# Smarttree_BMS_3_1.net
KiCad netlist of a schematic drawn in EAGLE
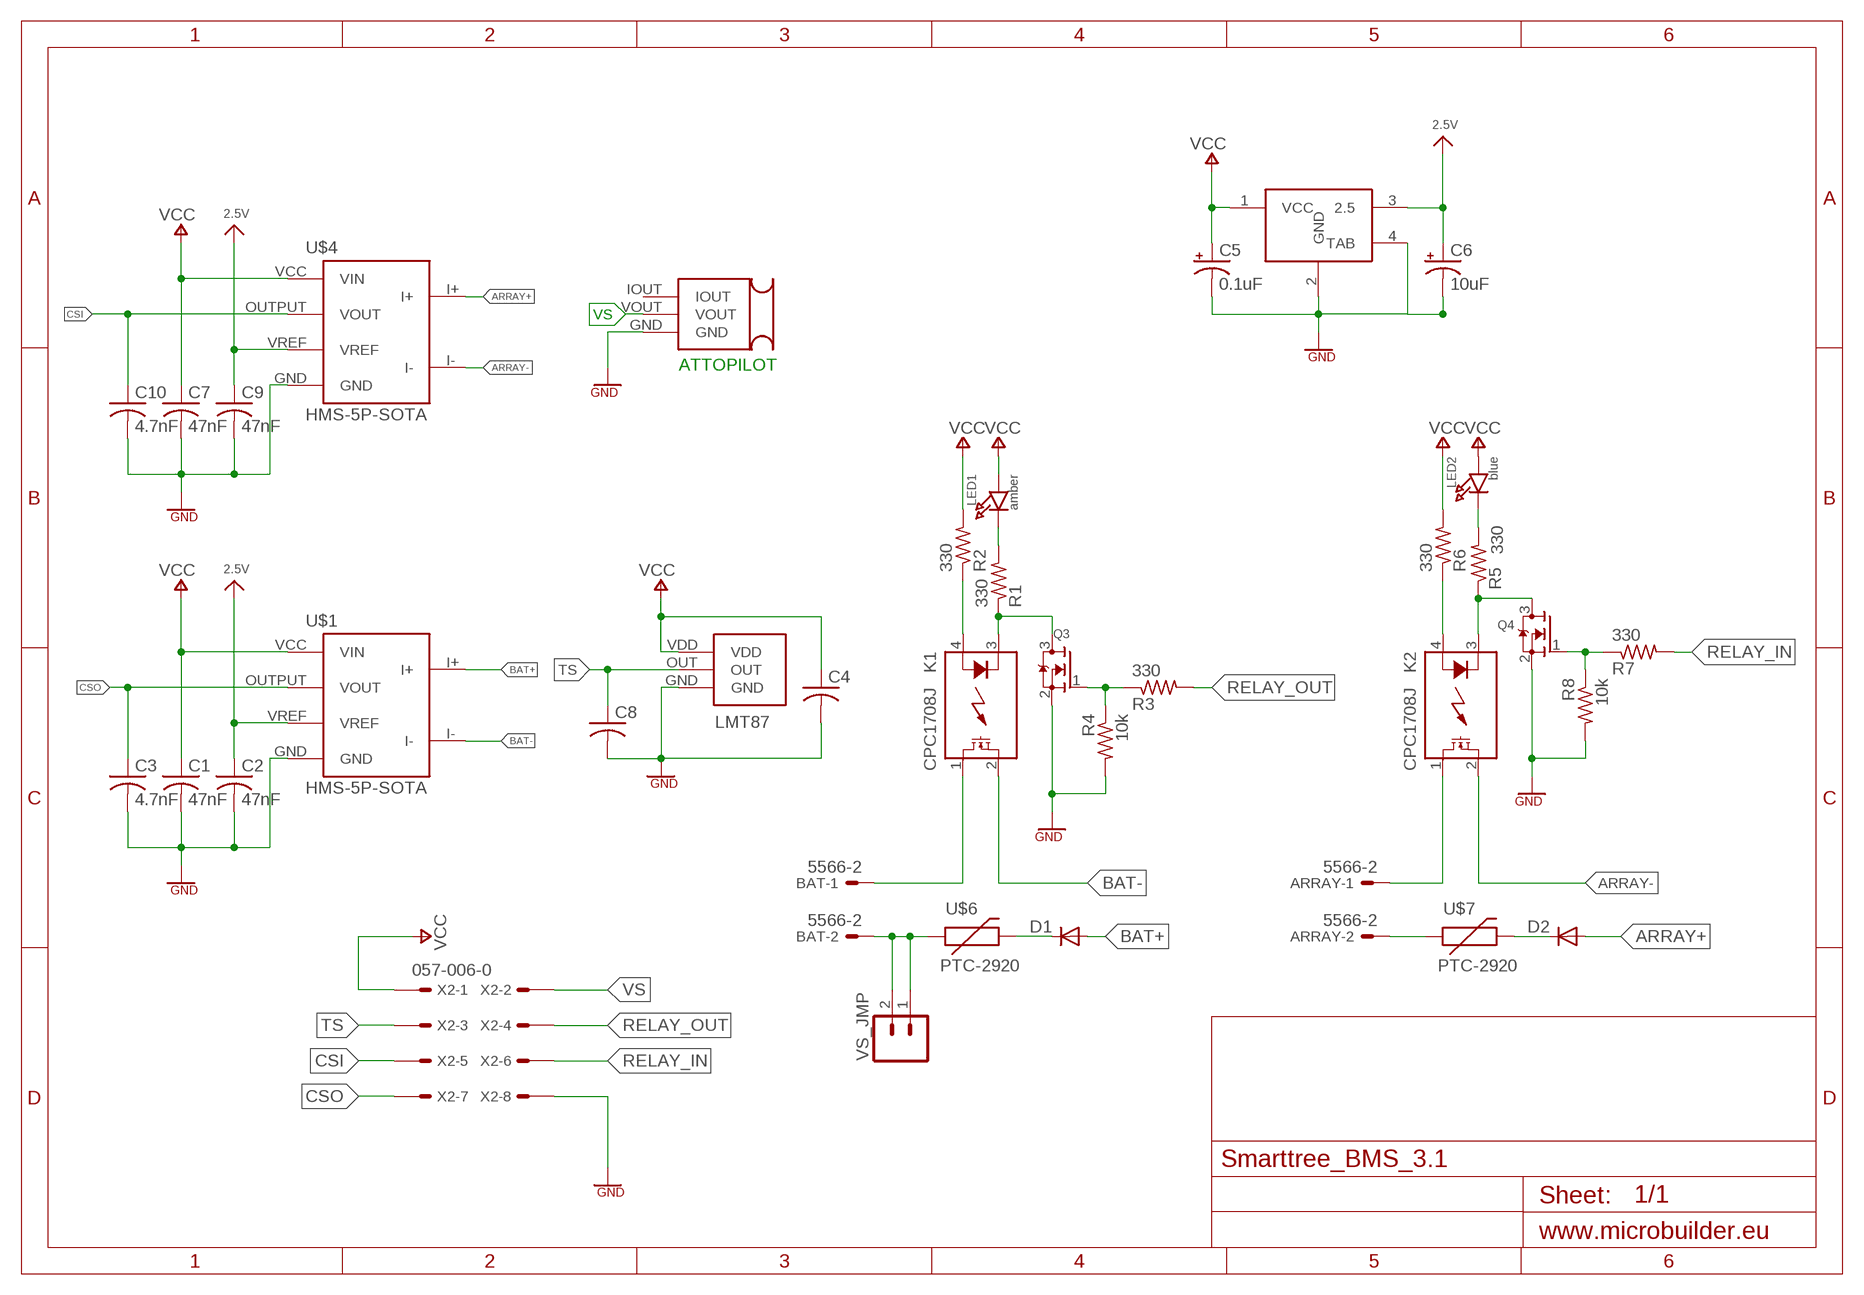
[diagram p0: schematic, sheet 1]

(export (version "E")
  (design (tool "Eeschema 10.0.6"))
  (components
    (comp (ref "ARRAY")
      (value "5566-2")
      (footprint "eagle-import:5566-2")
      (libsource (lib "eagle-import") (part "5566-2"))
    )
    (comp (ref "ATTOPILOT")
      (value "ATTOPILOT_VOLT")
      (footprint "eagle-import:TH_BKOT")
      (libsource (lib "eagle-import") (part "ATTOPILOT_VOLT"))
    )
    (comp (ref "BAT")
      (value "5566-2")
      (footprint "eagle-import:5566-2")
      (libsource (lib "eagle-import") (part "5566-2"))
    )
    (comp (ref "C1")
      (value "47nF")
      (footprint "eagle-import:C0805")
      (libsource (lib "eagle-import") (part "C-USC0805"))
    )
    (comp (ref "C2")
      (value "47nF")
      (footprint "eagle-import:C0805")
      (libsource (lib "eagle-import") (part "C-USC0805"))
    )
    (comp (ref "C3")
      (value "4.7nF")
      (footprint "eagle-import:C0805")
      (libsource (lib "eagle-import") (part "C-USC0805"))
    )
    (comp (ref "C4")
      (value "C-USC0805")
      (footprint "eagle-import:C0805")
      (libsource (lib "eagle-import") (part "C-USC0805"))
    )
    (comp (ref "C5")
      (value "0.1uF")
      (footprint "eagle-import:EIA3216")
      (libsource (lib "eagle-import") (part "10UF-TANT"))
    )
    (comp (ref "C6")
      (value "10uF")
      (footprint "eagle-import:EIA3216")
      (libsource (lib "eagle-import") (part "10UF-TANT"))
    )
    (comp (ref "C7")
      (value "47nF")
      (footprint "eagle-import:C0805")
      (libsource (lib "eagle-import") (part "C-USC0805"))
    )
    (comp (ref "C8")
      (value "C-USC0805")
      (footprint "eagle-import:C0805")
      (libsource (lib "eagle-import") (part "C-USC0805"))
    )
    (comp (ref "C9")
      (value "47nF")
      (footprint "eagle-import:C0805")
      (libsource (lib "eagle-import") (part "C-USC0805"))
    )
    (comp (ref "C10")
      (value "4.7nF")
      (footprint "eagle-import:C0805")
      (libsource (lib "eagle-import") (part "C-USC0805"))
    )
    (comp (ref "D1")
      (value "DIODE-SOD106-R")
      (footprint "eagle-import:SOD106-R")
      (libsource (lib "eagle-import") (part "DIODE-SOD106-R"))
    )
    (comp (ref "D2")
      (value "DIODE-SOD106-R")
      (footprint "eagle-import:SOD106-R")
      (libsource (lib "eagle-import") (part "DIODE-SOD106-R"))
    )
    (comp (ref "K1")
      (value "CPC1708J")
      (footprint "eagle-import:I4-PAC")
      (libsource (lib "eagle-import") (part "CPC1708J"))
    )
    (comp (ref "K2")
      (value "CPC1708J")
      (footprint "eagle-import:I4-PAC")
      (libsource (lib "eagle-import") (part "CPC1708J"))
    )
    (comp (ref "LED1")
      (value "amber")
      (footprint "eagle-import:CHIPLED_0805")
      (libsource (lib "eagle-import") (part "LED0805"))
    )
    (comp (ref "LED2")
      (value "blue")
      (footprint "eagle-import:CHIPLED_0805")
      (libsource (lib "eagle-import") (part "LED0805"))
    )
    (comp (ref "LM1117")
      (value "LM2937_SOT223")
      (footprint "eagle-import:SOT223")
      (libsource (lib "eagle-import") (part "LM2937_SOT223"))
    )
    (comp (ref "LMT87")
      (value "LMT87_PAC")
      (footprint "eagle-import:LMT87_TO")
      (libsource (lib "eagle-import") (part "LMT87_PAC"))
    )
    (comp (ref "Q3")
      (value "MOSFET-NREFLOW")
      (footprint "eagle-import:SOT23")
      (libsource (lib "eagle-import") (part "MOSFET-NREFLOW"))
    )
    (comp (ref "Q4")
      (value "MOSFET-NREFLOW")
      (footprint "eagle-import:SOT23")
      (libsource (lib "eagle-import") (part "MOSFET-NREFLOW"))
    )
    (comp (ref "R1")
      (value "330")
      (footprint "eagle-import:R0805")
      (libsource (lib "eagle-import") (part "R-US_R0805"))
    )
    (comp (ref "R2")
      (value "330")
      (footprint "eagle-import:R0805")
      (libsource (lib "eagle-import") (part "R-US_R0805"))
    )
    (comp (ref "R3")
      (value "330")
      (footprint "eagle-import:R0805")
      (libsource (lib "eagle-import") (part "R-US_R0805"))
    )
    (comp (ref "R4")
      (value "10k")
      (footprint "eagle-import:R0805")
      (libsource (lib "eagle-import") (part "R-US_R0805"))
    )
    (comp (ref "R5")
      (value "330")
      (footprint "eagle-import:R0805")
      (libsource (lib "eagle-import") (part "R-US_R0805"))
    )
    (comp (ref "R6")
      (value "330")
      (footprint "eagle-import:R0805")
      (libsource (lib "eagle-import") (part "R-US_R0805"))
    )
    (comp (ref "R7")
      (value "330")
      (footprint "eagle-import:R0805")
      (libsource (lib "eagle-import") (part "R-US_R0805"))
    )
    (comp (ref "R8")
      (value "10k")
      (footprint "eagle-import:R0805")
      (libsource (lib "eagle-import") (part "R-US_R0805"))
    )
    (comp (ref "U$1")
      (value "HMS-5P-SOTA")
      (footprint "eagle-import:SMD_CURR_SENSE")
      (libsource (lib "eagle-import") (part "HMS-5P-SOTA"))
    )
    (comp (ref "U$4")
      (value "HMS-5P-SOTA")
      (footprint "eagle-import:SMD_CURR_SENSE")
      (libsource (lib "eagle-import") (part "HMS-5P-SOTA"))
    )
    (comp (ref "U$6")
      (value "PTC-2920")
      (footprint "eagle-import:PTC-2920")
      (libsource (lib "eagle-import") (part "PTC-2920"))
    )
    (comp (ref "U$7")
      (value "PTC-2920")
      (footprint "eagle-import:PTC-2920")
      (libsource (lib "eagle-import") (part "PTC-2920"))
    )
    (comp (ref "VS_JMP")
      (value "M02")
      (footprint "eagle-import:1X02_LONGPADS")
      (libsource (lib "eagle-import") (part "M02"))
    )
    (comp (ref "X2")
      (value "057-006-0")
      (footprint "eagle-import:057-006-0")
      (libsource (lib "eagle-import") (part "057-006-0"))
    )
  )
  (nets
    (net (code "1") (name "2.5V") (class "Default")
      (node (ref "C2") (pin "1") (pinfunction "1_1") (pintype "passive"))
      (node (ref "C6") (pin "A") (pinfunction "+_A") (pintype "passive"))
      (node (ref "C9") (pin "1") (pinfunction "1_1") (pintype "passive"))
      (node (ref "LM1117") (pin "3") (pinfunction "2.5_3") (pintype "bidirectional"))
      (node (ref "U$1") (pin "VREF") (pinfunction "VREF_VREF") (pintype "bidirectional"))
      (node (ref "U$4") (pin "VREF") (pinfunction "VREF_VREF") (pintype "bidirectional"))
    )
    (net (code "2") (name "5V") (class "Default")
      (node (ref "C1") (pin "1") (pinfunction "1_1") (pintype "passive"))
      (node (ref "C4") (pin "1") (pinfunction "1_1") (pintype "passive"))
      (node (ref "C5") (pin "A") (pinfunction "+_A") (pintype "passive"))
      (node (ref "C7") (pin "1") (pinfunction "1_1") (pintype "passive"))
      (node (ref "LED1") (pin "A") (pinfunction "A_A") (pintype "passive"))
      (node (ref "LED2") (pin "A") (pinfunction "A_A") (pintype "passive"))
      (node (ref "LM1117") (pin "1") (pinfunction "VCC_1") (pintype "bidirectional"))
      (node (ref "LMT87") (pin "VDD") (pinfunction "VDD_VDD") (pintype "bidirectional"))
      (node (ref "R2") (pin "2") (pinfunction "2_2") (pintype "passive"))
      (node (ref "R6") (pin "2") (pinfunction "2_2") (pintype "passive"))
      (node (ref "U$1") (pin "VCC") (pinfunction "VIN_VCC") (pintype "bidirectional"))
      (node (ref "U$4") (pin "VCC") (pinfunction "VIN_VCC") (pintype "bidirectional"))
      (node (ref "X2") (pin "1") (pinfunction "S_1") (pintype "passive"))
    )
    (net (code "3") (name "ARRAY+") (class "Default")
      (node (ref "D2") (pin "A") (pinfunction "A_A") (pintype "passive"))
      (node (ref "U$4") (pin "I+") (pinfunction "I+_I+") (pintype "bidirectional"))
    )
    (net (code "4") (name "ARRAY-") (class "Default")
      (node (ref "K2") (pin "2") (pinfunction "DS2_2") (pintype "passive"))
      (node (ref "U$4") (pin "I-") (pinfunction "I-_I-") (pintype "bidirectional"))
    )
    (net (code "5") (name "BAT+") (class "Default")
      (node (ref "D1") (pin "A") (pinfunction "A_A") (pintype "passive"))
      (node (ref "U$1") (pin "I+") (pinfunction "I+_I+") (pintype "bidirectional"))
    )
    (net (code "6") (name "BAT-") (class "Default")
      (node (ref "K1") (pin "2") (pinfunction "DS2_2") (pintype "passive"))
      (node (ref "U$1") (pin "I-") (pinfunction "I-_I-") (pintype "bidirectional"))
    )
    (net (code "7") (name "CSI") (class "Default")
      (node (ref "C10") (pin "1") (pinfunction "1_1") (pintype "passive"))
      (node (ref "U$4") (pin "OUTPUT") (pinfunction "VOUT_OUTPUT") (pintype "bidirectional"))
      (node (ref "X2") (pin "5") (pinfunction "S_5") (pintype "passive"))
    )
    (net (code "8") (name "CSO") (class "Default")
      (node (ref "C3") (pin "1") (pinfunction "1_1") (pintype "passive"))
      (node (ref "U$1") (pin "OUTPUT") (pinfunction "VOUT_OUTPUT") (pintype "bidirectional"))
      (node (ref "X2") (pin "8") (pinfunction "S_8") (pintype "passive"))
    )
    (net (code "9") (name "GND") (class "Default")
      (node (ref "ATTOPILOT") (pin "GND") (pinfunction "GND_GND") (pintype "bidirectional"))
      (node (ref "C1") (pin "2") (pinfunction "2_2") (pintype "passive"))
      (node (ref "C10") (pin "2") (pinfunction "2_2") (pintype "passive"))
      (node (ref "C2") (pin "2") (pinfunction "2_2") (pintype "passive"))
      (node (ref "C3") (pin "2") (pinfunction "2_2") (pintype "passive"))
      (node (ref "C4") (pin "2") (pinfunction "2_2") (pintype "passive"))
      (node (ref "C5") (pin "C") (pinfunction "-_C") (pintype "passive"))
      (node (ref "C6") (pin "C") (pinfunction "-_C") (pintype "passive"))
      (node (ref "C7") (pin "2") (pinfunction "2_2") (pintype "passive"))
      (node (ref "C8") (pin "2") (pinfunction "2_2") (pintype "passive"))
      (node (ref "C9") (pin "2") (pinfunction "2_2") (pintype "passive"))
      (node (ref "LM1117") (pin "2") (pinfunction "GND_2") (pintype "bidirectional"))
      (node (ref "LM1117") (pin "4") (pinfunction "TAB_4") (pintype "bidirectional"))
      (node (ref "LMT87") (pin "GND") (pinfunction "GND_GND") (pintype "bidirectional"))
      (node (ref "Q3") (pin "2") (pinfunction "S_2") (pintype "bidirectional"))
      (node (ref "Q4") (pin "2") (pinfunction "S_2") (pintype "bidirectional"))
      (node (ref "R4") (pin "2") (pinfunction "2_2") (pintype "passive"))
      (node (ref "R8") (pin "2") (pinfunction "2_2") (pintype "passive"))
      (node (ref "U$1") (pin "GND") (pinfunction "GND_GND") (pintype "bidirectional"))
      (node (ref "U$4") (pin "GND") (pinfunction "GND_GND") (pintype "bidirectional"))
      (node (ref "X2") (pin "7") (pinfunction "S_7") (pintype "passive"))
    )
    (net (code "10") (name "Net-(ARRAYA-S)") (class "Default")
      (node (ref "ARRAY") (pin "1") (pinfunction "S_1") (pintype "passive"))
      (node (ref "K2") (pin "1") (pinfunction "DS1_1") (pintype "passive"))
    )
    (net (code "11") (name "Net-(ARRAYB-S)") (class "Default")
      (node (ref "ARRAY") (pin "2") (pinfunction "S_2") (pintype "passive"))
      (node (ref "U$7") (pin "1") (pinfunction "1_1") (pintype "bidirectional"))
    )
    (net (code "12") (name "Net-(BATA-S)") (class "Default")
      (node (ref "BAT") (pin "1") (pinfunction "S_1") (pintype "passive"))
      (node (ref "K1") (pin "1") (pinfunction "DS1_1") (pintype "passive"))
    )
    (net (code "13") (name "Net-(BATB-S)") (class "Default")
      (node (ref "BAT") (pin "2") (pinfunction "S_2") (pintype "passive"))
      (node (ref "U$6") (pin "1") (pinfunction "1_1") (pintype "bidirectional"))
      (node (ref "VS_JMP") (pin "1") (pinfunction "1_1") (pintype "passive"))
      (node (ref "VS_JMP") (pin "2") (pinfunction "2_2") (pintype "passive"))
    )
    (net (code "14") (name "Net-(D1-PadC)") (class "Default")
      (node (ref "D1") (pin "C") (pinfunction "C_C") (pintype "passive"))
      (node (ref "U$6") (pin "2") (pinfunction "2_2") (pintype "bidirectional"))
    )
    (net (code "15") (name "Net-(D2-PadC)") (class "Default")
      (node (ref "D2") (pin "C") (pinfunction "C_C") (pintype "passive"))
      (node (ref "U$7") (pin "2") (pinfunction "2_2") (pintype "bidirectional"))
    )
    (net (code "16") (name "Net-(K1-A)") (class "Default")
      (node (ref "K1") (pin "4") (pinfunction "A_4") (pintype "passive"))
      (node (ref "R2") (pin "1") (pinfunction "1_1") (pintype "passive"))
    )
    (net (code "17") (name "Net-(K1-K)") (class "Default")
      (node (ref "K1") (pin "3") (pinfunction "K_3") (pintype "passive"))
      (node (ref "Q3") (pin "3") (pinfunction "D_3") (pintype "bidirectional"))
      (node (ref "R1") (pin "1") (pinfunction "1_1") (pintype "passive"))
    )
    (net (code "18") (name "Net-(K2-A)") (class "Default")
      (node (ref "K2") (pin "4") (pinfunction "A_4") (pintype "passive"))
      (node (ref "R6") (pin "1") (pinfunction "1_1") (pintype "passive"))
    )
    (net (code "19") (name "Net-(K2-K)") (class "Default")
      (node (ref "K2") (pin "3") (pinfunction "K_3") (pintype "passive"))
      (node (ref "Q4") (pin "3") (pinfunction "D_3") (pintype "bidirectional"))
      (node (ref "R5") (pin "1") (pinfunction "1_1") (pintype "passive"))
    )
    (net (code "20") (name "Net-(LED1-PadC)") (class "Default")
      (node (ref "LED1") (pin "C") (pinfunction "C_C") (pintype "passive"))
      (node (ref "R1") (pin "2") (pinfunction "2_2") (pintype "passive"))
    )
    (net (code "21") (name "Net-(LED2-PadC)") (class "Default")
      (node (ref "LED2") (pin "C") (pinfunction "C_C") (pintype "passive"))
      (node (ref "R5") (pin "2") (pinfunction "2_2") (pintype "passive"))
    )
    (net (code "22") (name "Net-(Q3-G)") (class "Default")
      (node (ref "Q3") (pin "1") (pinfunction "G_1") (pintype "bidirectional"))
      (node (ref "R3") (pin "1") (pinfunction "1_1") (pintype "passive"))
      (node (ref "R4") (pin "1") (pinfunction "1_1") (pintype "passive"))
    )
    (net (code "23") (name "Net-(Q4-G)") (class "Default")
      (node (ref "Q4") (pin "1") (pinfunction "G_1") (pintype "bidirectional"))
      (node (ref "R7") (pin "1") (pinfunction "1_1") (pintype "passive"))
      (node (ref "R8") (pin "1") (pinfunction "1_1") (pintype "passive"))
    )
    (net (code "24") (name "RELAY_IN") (class "Default")
      (node (ref "R7") (pin "2") (pinfunction "2_2") (pintype "passive"))
      (node (ref "X2") (pin "6") (pinfunction "S_6") (pintype "passive"))
    )
    (net (code "25") (name "RELAY_OUT") (class "Default")
      (node (ref "R3") (pin "2") (pinfunction "2_2") (pintype "passive"))
      (node (ref "X2") (pin "4") (pinfunction "S_4") (pintype "passive"))
    )
    (net (code "26") (name "TS") (class "Default")
      (node (ref "C8") (pin "1") (pinfunction "1_1") (pintype "passive"))
      (node (ref "LMT87") (pin "OUT") (pinfunction "OUT_OUT") (pintype "bidirectional"))
      (node (ref "X2") (pin "3") (pinfunction "S_3") (pintype "passive"))
    )
    (net (code "27") (name "VS") (class "Default")
      (node (ref "ATTOPILOT") (pin "VOUT") (pinfunction "VOUT_VOUT") (pintype "bidirectional"))
      (node (ref "X2") (pin "2") (pinfunction "S_2") (pintype "passive"))
    )
    (net (code "28") (name "unconnected-(ATTOPILOT-PadIOUT)") (class "Default")
      (node (ref "ATTOPILOT") (pin "IOUT") (pinfunction "IOUT_IOUT") (pintype "bidirectional"))
    )
  )
)
